# NTC_Sense.net
KiCad netlist of a schematic drawn in Altium Designer
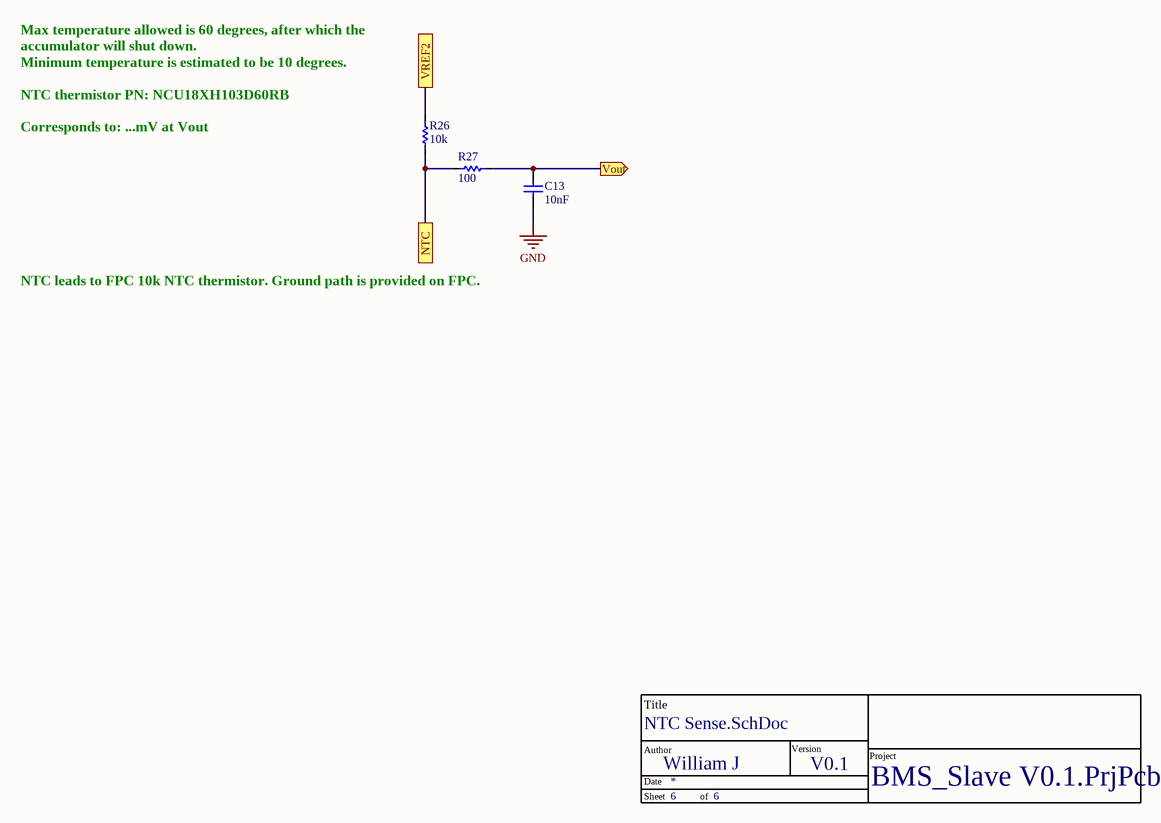
[diagram p0: NTC Sense.SchDoc]

(export (version "E")
  (design (tool "Eeschema 10.0.6"))
  (components
    (comp (ref "*") (value "TitleBlock") (libsource (lib "SchematicLib") (part "TitleBlock")))
    (comp (ref "C13")
      (value "10nF")
      (footprint "C_0603")
      (description "Capacitor")
      (fields (field (name "Comment") "C"))
      (libsource (lib "Passives") (part "Capacitor"))
    )
    (comp (ref "R26")
      (value "10k")
      (footprint "R-0603")
      (description "Resistor")
      (libsource (lib "Passives") (part "Resistor"))
    )
    (comp (ref "R27")
      (value "100")
      (footprint "R-0603")
      (description "Resistor")
      (libsource (lib "Passives") (part "Resistor"))
    )
  )
  (nets
    (net (code "1") (name "/NTC") (class "Default")
      (node (ref "R26") (pin "1") (pinfunction "1_1") (pintype "passive"))
      (node (ref "R27") (pin "2") (pinfunction "2_2") (pintype "passive"))
    )
    (net (code "2") (name "/VREF2") (class "Default")
      (node (ref "R26") (pin "2") (pinfunction "2_2") (pintype "passive"))
    )
    (net (code "3") (name "/Vout") (class "Default")
      (node (ref "C13") (pin "2") (pinfunction "2_2") (pintype "passive"))
      (node (ref "R27") (pin "1") (pinfunction "1_1") (pintype "passive"))
    )
    (net (code "4") (name "GND") (class "Default")
      (node (ref "C13") (pin "1") (pinfunction "1_1") (pintype "passive"))
    )
  )
)
